# SoundSensor.net
KiCad netlist of a schematic drawn in EAGLE
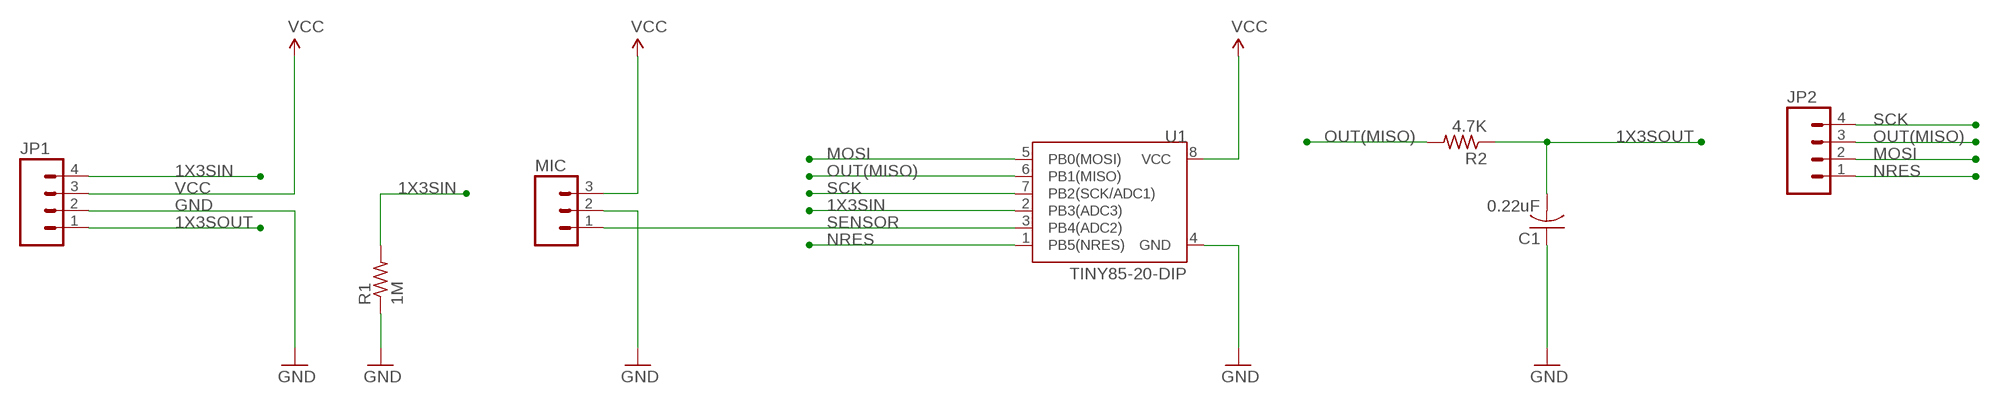
[diagram p0: schematic, sheet 1]

(export (version "E")
  (design (tool "Eeschema 10.0.6"))
  (components
    (comp (ref "C1")
      (value "0.22uF")
      (footprint "eagle-import:C0402")
      (libsource (lib "eagle-import") (part "C-USC0402"))
    )
    (comp (ref "JP1")
      (value "M04PTH")
      (footprint "eagle-import:1X04")
      (libsource (lib "eagle-import") (part "M04PTH"))
    )
    (comp (ref "JP2")
      (value "M04PTH")
      (footprint "eagle-import:1X04")
      (libsource (lib "eagle-import") (part "M04PTH"))
    )
    (comp (ref "MIC")
      (value "M03PTH")
      (footprint "eagle-import:1X03")
      (libsource (lib "eagle-import") (part "M03PTH"))
    )
    (comp (ref "R1")
      (value "1M")
      (footprint "eagle-import:R0603")
      (libsource (lib "eagle-import") (part "R-US_R0603"))
    )
    (comp (ref "R2")
      (value "4.7K")
      (footprint "eagle-import:R0603")
      (libsource (lib "eagle-import") (part "R-US_R0603"))
    )
    (comp (ref "U1")
      (value "TINY85-20-DIP")
      (footprint "eagle-import:DIP08")
      (libsource (lib "eagle-import") (part "ATTINY45TINY85-20-DIP"))
    )
  )
  (nets
    (net (code "1") (name "/1X3SIN") (class "Default")
      (node (ref "JP1") (pin "4") (pinfunction "4_4") (pintype "passive"))
      (node (ref "R1") (pin "2") (pinfunction "2_2") (pintype "passive"))
      (node (ref "U1") (pin "2") (pinfunction "PB3(ADC3)_2") (pintype "bidirectional"))
    )
    (net (code "2") (name "/1X3SOUT") (class "Default")
      (node (ref "C1") (pin "2") (pinfunction "2_2") (pintype "passive"))
      (node (ref "JP1") (pin "1") (pinfunction "1_1") (pintype "passive"))
      (node (ref "R2") (pin "1") (pinfunction "1_1") (pintype "passive"))
    )
    (net (code "3") (name "/MOSI") (class "Default")
      (node (ref "JP2") (pin "2") (pinfunction "2_2") (pintype "passive"))
      (node (ref "U1") (pin "5") (pinfunction "PB0(MOSI)_5") (pintype "bidirectional"))
    )
    (net (code "4") (name "/NRES") (class "Default")
      (node (ref "JP2") (pin "1") (pinfunction "1_1") (pintype "passive"))
      (node (ref "U1") (pin "1") (pinfunction "PB5(NRES)_1") (pintype "bidirectional"))
    )
    (net (code "5") (name "/OUT(MISO)") (class "Default")
      (node (ref "JP2") (pin "3") (pinfunction "3_3") (pintype "passive"))
      (node (ref "R2") (pin "2") (pinfunction "2_2") (pintype "passive"))
      (node (ref "U1") (pin "6") (pinfunction "PB1(MISO)_6") (pintype "bidirectional"))
    )
    (net (code "6") (name "/SCK") (class "Default")
      (node (ref "JP2") (pin "4") (pinfunction "4_4") (pintype "passive"))
      (node (ref "U1") (pin "7") (pinfunction "PB2(SCK/ADC1)_7") (pintype "bidirectional"))
    )
    (net (code "7") (name "/SENSOR") (class "Default")
      (node (ref "MIC") (pin "1") (pinfunction "1_1") (pintype "passive"))
      (node (ref "U1") (pin "3") (pinfunction "PB4(ADC2)_3") (pintype "bidirectional"))
    )
    (net (code "8") (name "GND") (class "Default")
      (node (ref "C1") (pin "1") (pinfunction "1_1") (pintype "passive"))
      (node (ref "JP1") (pin "2") (pinfunction "2_2") (pintype "passive"))
      (node (ref "MIC") (pin "2") (pinfunction "2_2") (pintype "passive"))
      (node (ref "R1") (pin "1") (pinfunction "1_1") (pintype "passive"))
      (node (ref "U1") (pin "4") (pinfunction "GND_4") (pintype "bidirectional"))
    )
    (net (code "9") (name "VCC") (class "Default")
      (node (ref "JP1") (pin "3") (pinfunction "3_3") (pintype "passive"))
      (node (ref "MIC") (pin "3") (pinfunction "3_3") (pintype "passive"))
      (node (ref "U1") (pin "8") (pinfunction "VCC_8") (pintype "bidirectional"))
    )
  )
)
